# power_supply.net
KiCad netlist of a schematic drawn in Altium Designer
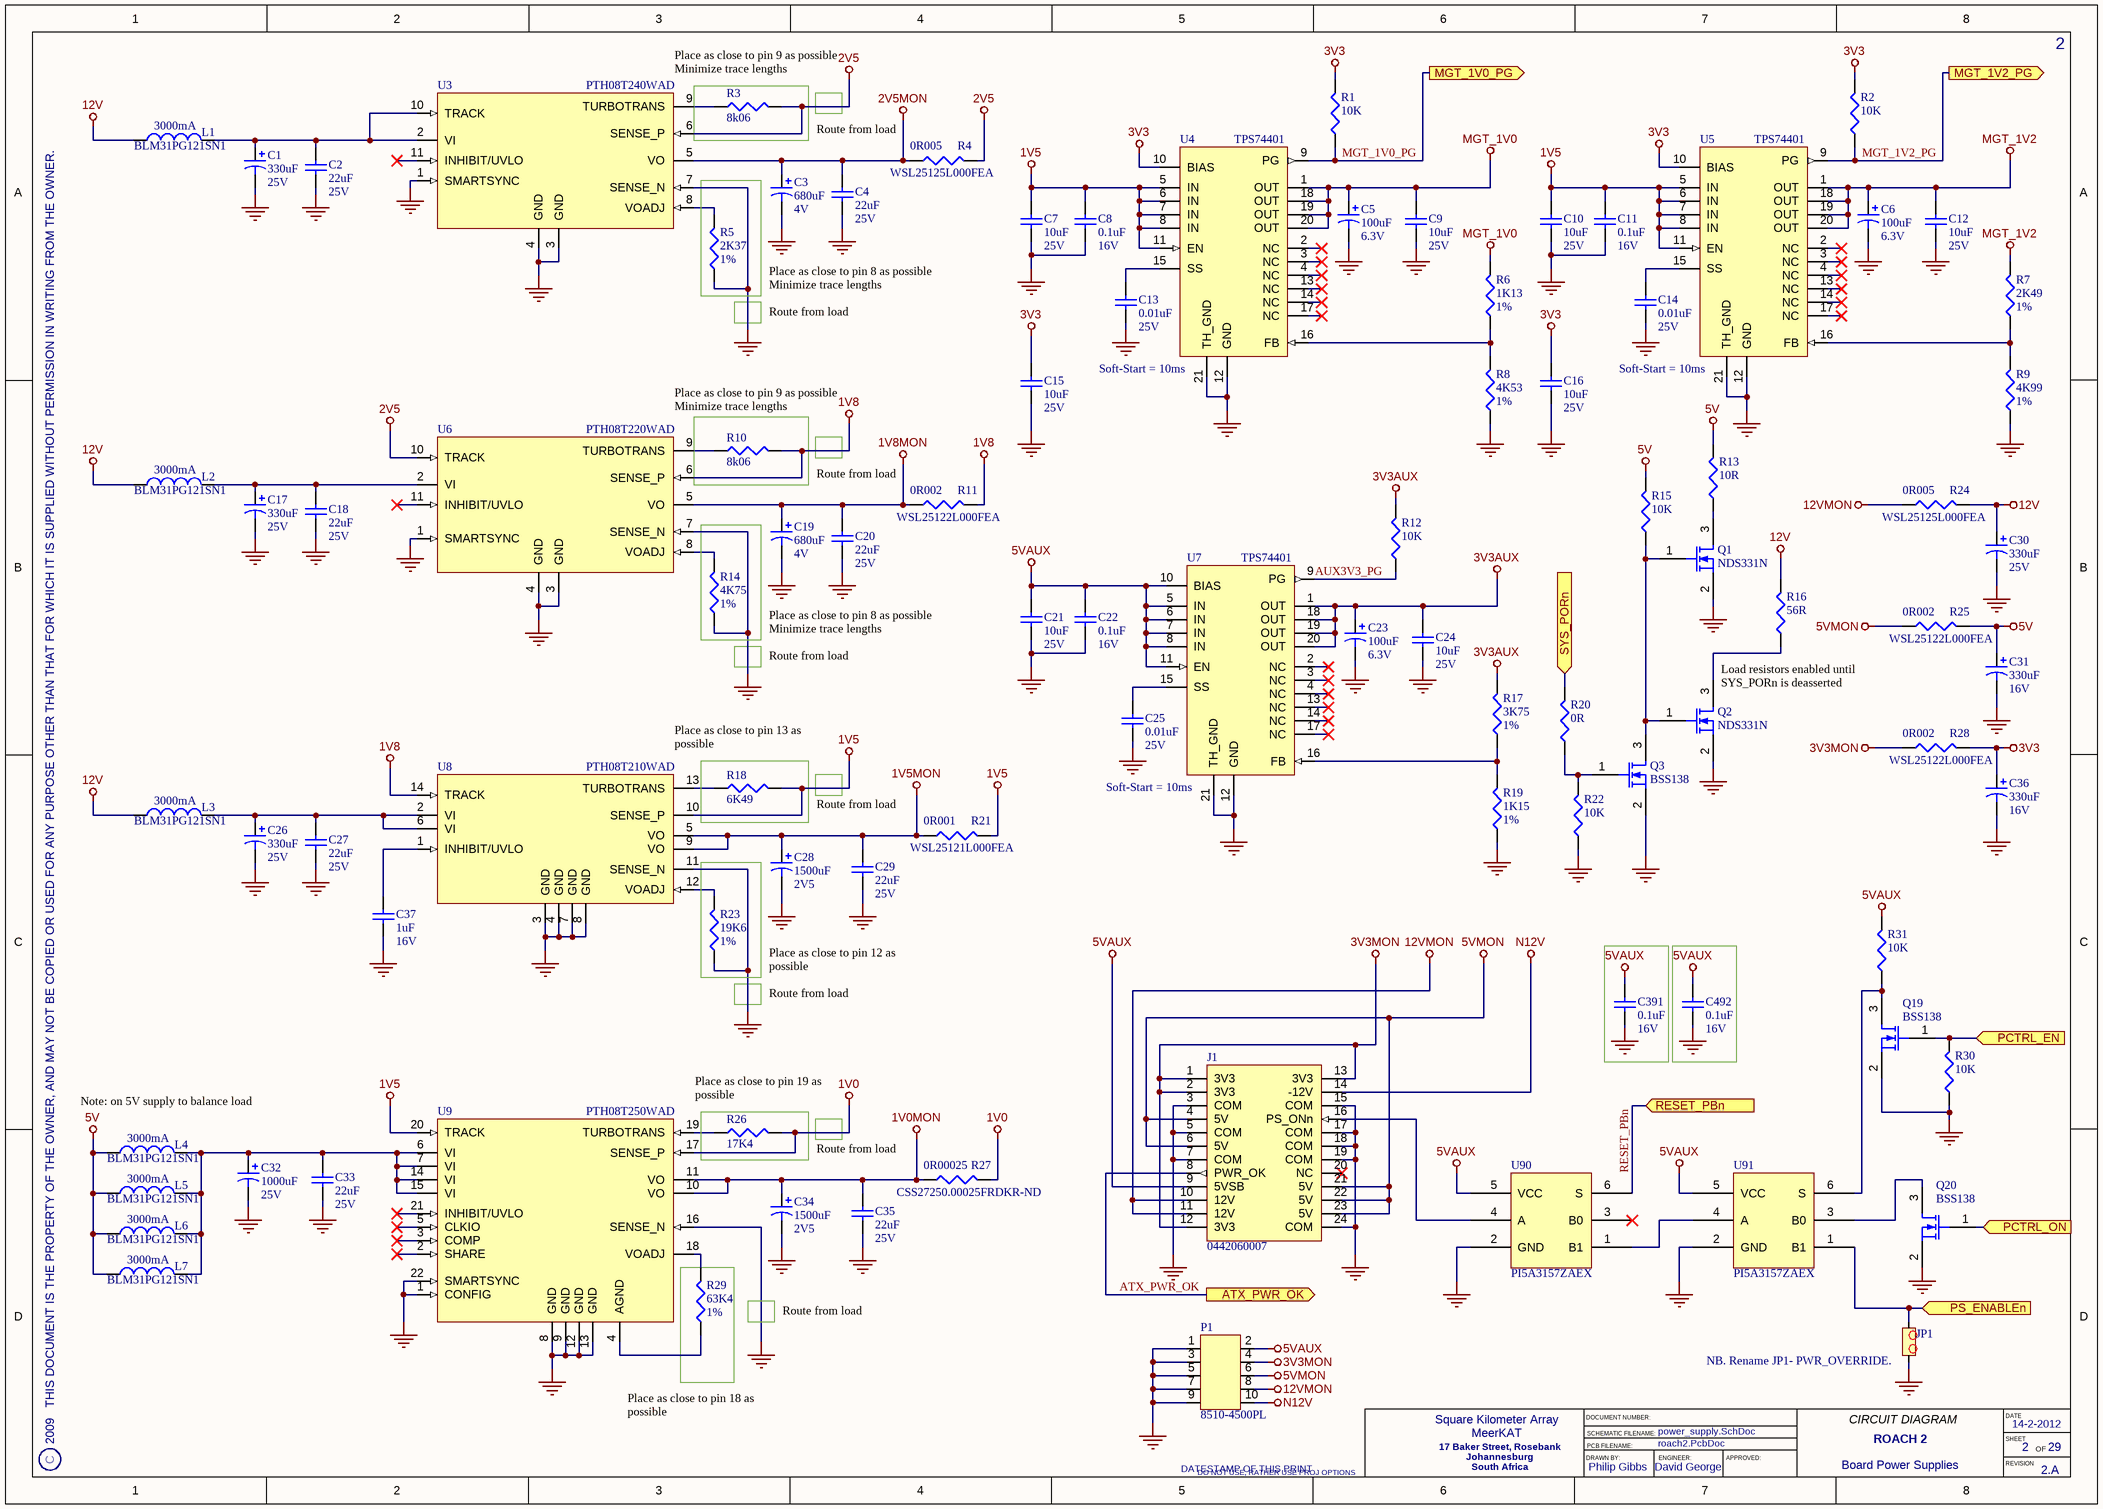
[diagram p0: power_supply.SchDoc]

(export (version "E")
  (design (tool "Eeschema 10.0.6"))
  (components
    (comp (ref "C1")
      (value "330uF")
      (footprint "EEE1CA331UP")
      (description "330uF, Surface Mount, Radial, Aluminium Electrolytic Capacitor")
      (fields
        (field (name "RATING") "25V")
        (field (name "MANUFACTURER") "PANASONIC-ECG")
        (field (name "PARTNUM") "EEE1EA331UP")
      )
      (libsource (lib "altium_db") (part "CapPol"))
    )
    (comp (ref "C2")
      (value "22uF")
      (footprint "CAPC3225X270L")
      (description "22uF, Ceramic Capacitor")
      (fields
        (field (name "RATING") "25V")
        (field (name "MANUFACTURER") "MURATA")
        (field (name "PARTNUM") "GRM32ER61E226ME15L")
      )
      (libsource (lib "altium_db") (part "CapStd"))
    )
    (comp (ref "C3")
      (value "680uF")
      (footprint "CAPMP7343X430L")
      (description "680uF, Conductive Polymer Chip Capacitor")
      (fields
        (field (name "RATING") "4V")
        (field (name "MANUFACTURER") "KEMET")
        (field (name "PARTNUM") "T520Y687M004ATE015")
      )
      (libsource (lib "altium_db") (part "CapPol"))
    )
    (comp (ref "C4")
      (value "22uF")
      (footprint "CAPC3225X270L")
      (description "22uF, Ceramic Capacitor")
      (fields
        (field (name "RATING") "25V")
        (field (name "MANUFACTURER") "MURATA")
        (field (name "PARTNUM") "GRM32ER61E226ME15L")
      )
      (libsource (lib "altium_db") (part "CapStd"))
    )
    (comp (ref "C5")
      (value "100uF")
      (footprint "CAPMP3528X210L")
      (description "100uF, Low ESR, Tantalum Capacitor")
      (fields
        (field (name "RATING") "6.3V")
        (field (name "MANUFACTURER") "AVX")
        (field (name "PARTNUM") "TPSB107M006R0200")
      )
      (libsource (lib "altium_db") (part "CapPol"))
    )
    (comp (ref "C6")
      (value "100uF")
      (footprint "CAPMP3528X210L")
      (description "100uF, Low ESR, Tantalum Capacitor")
      (fields
        (field (name "RATING") "6.3V")
        (field (name "MANUFACTURER") "AVX")
        (field (name "PARTNUM") "TPSB107M006R0200")
      )
      (libsource (lib "altium_db") (part "CapPol"))
    )
    (comp (ref "C7")
      (value "10uF")
      (footprint "CAPC3225X200L")
      (description "10uF, Ceramic Capacitor")
      (fields
        (field (name "RATING") "25V")
        (field (name "MANUFACTURER") "MURATA")
        (field (name "PARTNUM") "GRM32DR61E106KA12L")
      )
      (libsource (lib "altium_db") (part "CapStd"))
    )
    (comp (ref "C8")
      (value "0.1uF")
      (footprint "CAPC1005X60L")
      (description "0.1uF, Ceramic Capacitor")
      (fields
        (field (name "RATING") "16V")
        (field (name "MANUFACTURER") "VENKEL")
        (field (name "PARTNUM") "C0402X7R160-104KN")
      )
      (libsource (lib "altium_db") (part "CapStd"))
    )
    (comp (ref "C9")
      (value "10uF")
      (footprint "CAPC3225X200L")
      (description "10uF, Ceramic Capacitor")
      (fields
        (field (name "RATING") "25V")
        (field (name "MANUFACTURER") "MURATA")
        (field (name "PARTNUM") "GRM32DR61E106KA12L")
      )
      (libsource (lib "altium_db") (part "CapStd"))
    )
    (comp (ref "C10")
      (value "10uF")
      (footprint "CAPC3225X200L")
      (description "10uF, Ceramic Capacitor")
      (fields
        (field (name "RATING") "25V")
        (field (name "MANUFACTURER") "MURATA")
        (field (name "PARTNUM") "GRM32DR61E106KA12L")
      )
      (libsource (lib "altium_db") (part "CapStd"))
    )
    (comp (ref "C11")
      (value "0.1uF")
      (footprint "CAPC1005X60L")
      (description "0.1uF, Ceramic Capacitor")
      (fields
        (field (name "RATING") "16V")
        (field (name "MANUFACTURER") "VENKEL")
        (field (name "PARTNUM") "C0402X7R160-104KN")
      )
      (libsource (lib "altium_db") (part "CapStd"))
    )
    (comp (ref "C12")
      (value "10uF")
      (footprint "CAPC3225X200L")
      (description "10uF, Ceramic Capacitor")
      (fields
        (field (name "RATING") "25V")
        (field (name "MANUFACTURER") "MURATA")
        (field (name "PARTNUM") "GRM32DR61E106KA12L")
      )
      (libsource (lib "altium_db") (part "CapStd"))
    )
    (comp (ref "C13")
      (value "0.01uF")
      (footprint "CAPC1005X55L")
      (description "0.01uF, Ceramic Capacitor")
      (fields
        (field (name "RATING") "25V")
        (field (name "MANUFACTURER") "MURATA")
        (field (name "PARTNUM") "GRM155R71E103KA01D")
      )
      (libsource (lib "altium_db") (part "CapStd"))
    )
    (comp (ref "C14")
      (value "0.01uF")
      (footprint "CAPC1005X55L")
      (description "0.01uF, Ceramic Capacitor")
      (fields
        (field (name "RATING") "25V")
        (field (name "MANUFACTURER") "MURATA")
        (field (name "PARTNUM") "GRM155R71E103KA01D")
      )
      (libsource (lib "altium_db") (part "CapStd"))
    )
    (comp (ref "C15")
      (value "10uF")
      (footprint "CAPC3225X200L")
      (description "10uF, Ceramic Capacitor")
      (fields
        (field (name "RATING") "25V")
        (field (name "MANUFACTURER") "MURATA")
        (field (name "PARTNUM") "GRM32DR61E106KA12L")
      )
      (libsource (lib "altium_db") (part "CapStd"))
    )
    (comp (ref "C16")
      (value "10uF")
      (footprint "CAPC3225X200L")
      (description "10uF, Ceramic Capacitor")
      (fields
        (field (name "RATING") "25V")
        (field (name "MANUFACTURER") "MURATA")
        (field (name "PARTNUM") "GRM32DR61E106KA12L")
      )
      (libsource (lib "altium_db") (part "CapStd"))
    )
    (comp (ref "C17")
      (value "330uF")
      (footprint "EEE1CA331UP")
      (description "330uF, Surface Mount, Radial, Aluminium Electrolytic Capacitor")
      (fields
        (field (name "RATING") "25V")
        (field (name "MANUFACTURER") "PANASONIC-ECG")
        (field (name "PARTNUM") "EEE1EA331UP")
      )
      (libsource (lib "altium_db") (part "CapPol"))
    )
    (comp (ref "C18")
      (value "22uF")
      (footprint "CAPC3225X270L")
      (description "22uF, Ceramic Capacitor")
      (fields
        (field (name "RATING") "25V")
        (field (name "MANUFACTURER") "MURATA")
        (field (name "PARTNUM") "GRM32ER61E226ME15L")
      )
      (libsource (lib "altium_db") (part "CapStd"))
    )
    (comp (ref "C19")
      (value "680uF")
      (footprint "CAPMP7343X430L")
      (description "680uF, Conductive Polymer Chip Capacitor")
      (fields
        (field (name "RATING") "4V")
        (field (name "MANUFACTURER") "KEMET")
        (field (name "PARTNUM") "T520Y687M004ATE015")
      )
      (libsource (lib "altium_db") (part "CapPol"))
    )
    (comp (ref "C20")
      (value "22uF")
      (footprint "CAPC3225X270L")
      (description "22uF, Ceramic Capacitor")
      (fields
        (field (name "RATING") "25V")
        (field (name "MANUFACTURER") "MURATA")
        (field (name "PARTNUM") "GRM32ER61E226ME15L")
      )
      (libsource (lib "altium_db") (part "CapStd"))
    )
    (comp (ref "C21")
      (value "10uF")
      (footprint "CAPC3225X200L")
      (description "10uF, Ceramic Capacitor")
      (fields
        (field (name "RATING") "25V")
        (field (name "MANUFACTURER") "MURATA")
        (field (name "PARTNUM") "GRM32DR61E106KA12L")
      )
      (libsource (lib "altium_db") (part "CapStd"))
    )
    (comp (ref "C22")
      (value "0.1uF")
      (footprint "CAPC1005X60L")
      (description "0.1uF, Ceramic Capacitor")
      (fields
        (field (name "RATING") "16V")
        (field (name "MANUFACTURER") "VENKEL")
        (field (name "PARTNUM") "C0402X7R160-104KN")
      )
      (libsource (lib "altium_db") (part "CapStd"))
    )
    (comp (ref "C23")
      (value "100uF")
      (footprint "CAPMP3528X210L")
      (description "100uF, Low ESR, Tantalum Capacitor")
      (fields
        (field (name "RATING") "6.3V")
        (field (name "MANUFACTURER") "AVX")
        (field (name "PARTNUM") "TPSB107M006R0200")
      )
      (libsource (lib "altium_db") (part "CapPol"))
    )
    (comp (ref "C24")
      (value "10uF")
      (footprint "CAPC3225X200L")
      (description "10uF, Ceramic Capacitor")
      (fields
        (field (name "RATING") "25V")
        (field (name "MANUFACTURER") "MURATA")
        (field (name "PARTNUM") "GRM32DR61E106KA12L")
      )
      (libsource (lib "altium_db") (part "CapStd"))
    )
    (comp (ref "C25")
      (value "0.01uF")
      (footprint "CAPC1005X55L")
      (description "0.01uF, Ceramic Capacitor")
      (fields
        (field (name "RATING") "25V")
        (field (name "MANUFACTURER") "MURATA")
        (field (name "PARTNUM") "GRM155R71E103KA01D")
      )
      (libsource (lib "altium_db") (part "CapStd"))
    )
    (comp (ref "C26")
      (value "330uF")
      (footprint "EEE1CA331UP")
      (description "330uF, Surface Mount, Radial, Aluminium Electrolytic Capacitor")
      (fields
        (field (name "RATING") "25V")
        (field (name "MANUFACTURER") "PANASONIC-ECG")
        (field (name "PARTNUM") "EEE1EA331UP")
      )
      (libsource (lib "altium_db") (part "CapPol"))
    )
    (comp (ref "C27")
      (value "22uF")
      (footprint "CAPC3225X270L")
      (description "22uF, Ceramic Capacitor")
      (fields
        (field (name "RATING") "25V")
        (field (name "MANUFACTURER") "MURATA")
        (field (name "PARTNUM") "GRM32ER61E226ME15L")
      )
      (libsource (lib "altium_db") (part "CapStd"))
    )
    (comp (ref "C28")
      (value "1500uF")
      (footprint "CAPMP7343X430L")
      (description "1500uF, Conductive Polymer Chip Capacitor")
      (fields
        (field (name "RATING") "2V5")
        (field (name "MANUFACTURER") "KEMET")
        (field (name "PARTNUM") "T530X158M2R5ATE005")
      )
      (libsource (lib "altium_db") (part "CapPol"))
    )
    (comp (ref "C29")
      (value "22uF")
      (footprint "CAPC3225X270L")
      (description "22uF, Ceramic Capacitor")
      (fields
        (field (name "RATING") "25V")
        (field (name "MANUFACTURER") "MURATA")
        (field (name "PARTNUM") "GRM32ER61E226ME15L")
      )
      (libsource (lib "altium_db") (part "CapStd"))
    )
    (comp (ref "C30")
      (value "330uF")
      (footprint "EEE1CA331UP")
      (description "330uF, Surface Mount, Radial, Aluminium Electrolytic Capacitor")
      (fields
        (field (name "RATING") "25V")
        (field (name "MANUFACTURER") "PANASONIC-ECG")
        (field (name "PARTNUM") "EEE1EA331UP")
      )
      (libsource (lib "altium_db") (part "CapPol"))
    )
    (comp (ref "C31")
      (value "330uF")
      (footprint "CAPMP7263X380L")
      (description "330uF, Solid Tantalum Chip Capacitor")
      (fields
        (field (name "RATING") "16V")
        (field (name "MANUFACTURER") "VISHAY")
        (field (name "PARTNUM") "594D337X0016R2T")
      )
      (libsource (lib "altium_db") (part "CapPol"))
    )
    (comp (ref "C32")
      (value "1000uF")
      (footprint "CAPPRD750W80D1600H1500P")
      (description "1000uF, Aluminium Electrolytic Capacitor")
      (fields
        (field (name "RATING") "25V")
        (field (name "MANUFACTURER") "PANASONIC-ECG")
        (field (name "PARTNUM") "EEUFC1E102S")
      )
      (libsource (lib "altium_db") (part "CapPol"))
    )
    (comp (ref "C33")
      (value "22uF")
      (footprint "CAPC3225X270L")
      (description "22uF, Ceramic Capacitor")
      (fields
        (field (name "RATING") "25V")
        (field (name "MANUFACTURER") "MURATA")
        (field (name "PARTNUM") "GRM32ER61E226ME15L")
      )
      (libsource (lib "altium_db") (part "CapStd"))
    )
    (comp (ref "C34")
      (value "1500uF")
      (footprint "CAPMP7343X430L")
      (description "1500uF, Conductive Polymer Chip Capacitor")
      (fields
        (field (name "RATING") "2V5")
        (field (name "MANUFACTURER") "KEMET")
        (field (name "PARTNUM") "T530X158M2R5ATE005")
      )
      (libsource (lib "altium_db") (part "CapPol"))
    )
    (comp (ref "C35")
      (value "22uF")
      (footprint "CAPC3225X270L")
      (description "22uF, Ceramic Capacitor")
      (fields
        (field (name "RATING") "25V")
        (field (name "MANUFACTURER") "MURATA")
        (field (name "PARTNUM") "GRM32ER61E226ME15L")
      )
      (libsource (lib "altium_db") (part "CapStd"))
    )
    (comp (ref "C36")
      (value "330uF")
      (footprint "CAPMP7263X380L")
      (description "330uF, Solid Tantalum Chip Capacitor")
      (fields
        (field (name "RATING") "16V")
        (field (name "MANUFACTURER") "VISHAY")
        (field (name "PARTNUM") "594D337X0016R2T")
      )
      (libsource (lib "altium_db") (part "CapPol"))
    )
    (comp (ref "C37")
      (value "1uF")
      (footprint "CAPC2012X127L")
      (description "1uF, Ceramic Capacitor")
      (fields
        (field (name "MANUFACTURER") "MURATA")
        (field (name "PARTNUM") "GRM21BR61C105KA01L")
        (field (name "RATING") "16V")
      )
      (libsource (lib "altium_db") (part "CapStd"))
    )
    (comp (ref "C391")
      (value "0.1uF")
      (footprint "CAPC1005X60L")
      (description "0.1uF, Ceramic Capacitor")
      (fields
        (field (name "RATING") "16V")
        (field (name "MANUFACTURER") "VENKEL")
        (field (name "PARTNUM") "C0402X7R160-104KN")
      )
      (libsource (lib "altium_db") (part "CapStd"))
    )
    (comp (ref "C492")
      (value "0.1uF")
      (footprint "CAPC1005X60L")
      (description "0.1uF, Ceramic Capacitor")
      (fields
        (field (name "RATING") "16V")
        (field (name "MANUFACTURER") "VENKEL")
        (field (name "PARTNUM") "C0402X7R160-104KN")
      )
      (libsource (lib "altium_db") (part "CapStd"))
    )
    (comp (ref "J1")
      (value "0442060007")
      (footprint "MOLEX_0442060007")
      (description "24-Pin ATX Connector")
      (fields (field (name "PARTNUM") "0442060007") (field (name "MANUFACTURER") "Molex"))
      (libsource (lib "altium_db") (part "0442060007"))
    )
    (comp (ref "JP1")
      (value "0022032021")
      (footprint "MOLEX_0022032021")
      (description "1x2, 2.56mm, Header/Jumper")
      (fields (field (name "MANUFACTURER") "Molex"))
      (libsource (lib "altium_db") (part "con_hdr_1x2"))
    )
    (comp (ref "L1")
      (value "120R")
      (footprint "INDC3216X130L")
      (description "120 Ohm, Chip Ferrite Brad")
      (fields
        (field (name "RATING") "3000mA")
        (field (name "MANUFACTURER") "Murata")
        (field (name "PARTNUM") "BLM31PG121SN1")
        (field (name "TOLERANCE") "25%")
      )
      (libsource (lib "altium_db") (part "IndStd"))
    )
    (comp (ref "L2")
      (value "120R")
      (footprint "INDC3216X130L")
      (description "120 Ohm, Chip Ferrite Brad")
      (fields
        (field (name "RATING") "3000mA")
        (field (name "MANUFACTURER") "Murata")
        (field (name "PARTNUM") "BLM31PG121SN1")
        (field (name "TOLERANCE") "25%")
      )
      (libsource (lib "altium_db") (part "IndStd"))
    )
    (comp (ref "L3")
      (value "120R")
      (footprint "INDC3216X130L")
      (description "120 Ohm, Chip Ferrite Brad")
      (fields
        (field (name "RATING") "3000mA")
        (field (name "MANUFACTURER") "Murata")
        (field (name "PARTNUM") "BLM31PG121SN1")
        (field (name "TOLERANCE") "25%")
      )
      (libsource (lib "altium_db") (part "IndStd"))
    )
    (comp (ref "L4")
      (value "120R")
      (footprint "INDC3216X130L")
      (description "120 Ohm, Chip Ferrite Brad")
      (fields
        (field (name "RATING") "3000mA")
        (field (name "MANUFACTURER") "Murata")
        (field (name "PARTNUM") "BLM31PG121SN1")
        (field (name "TOLERANCE") "25%")
      )
      (libsource (lib "altium_db") (part "IndStd"))
    )
    (comp (ref "L5")
      (value "120R")
      (footprint "INDC3216X130L")
      (description "120 Ohm, Chip Ferrite Brad")
      (fields
        (field (name "RATING") "3000mA")
        (field (name "MANUFACTURER") "Murata")
        (field (name "PARTNUM") "BLM31PG121SN1")
        (field (name "TOLERANCE") "25%")
      )
      (libsource (lib "altium_db") (part "IndStd"))
    )
    (comp (ref "L6")
      (value "120R")
      (footprint "INDC3216X130L")
      (description "120 Ohm, Chip Ferrite Brad")
      (fields
        (field (name "RATING") "3000mA")
        (field (name "MANUFACTURER") "Murata")
        (field (name "PARTNUM") "BLM31PG121SN1")
        (field (name "TOLERANCE") "25%")
      )
      (libsource (lib "altium_db") (part "IndStd"))
    )
    (comp (ref "L7")
      (value "120R")
      (footprint "INDC3216X130L")
      (description "120 Ohm, Chip Ferrite Brad")
      (fields
        (field (name "RATING") "3000mA")
        (field (name "MANUFACTURER") "Murata")
        (field (name "PARTNUM") "BLM31PG121SN1")
        (field (name "TOLERANCE") "25%")
      )
      (libsource (lib "altium_db") (part "IndStd"))
    )
    (comp (ref "P1")
      (value "8510-4500PL")
      (footprint "3M_8510-4500PL")
      (description "2x5, 2.54 mm Pitch, Through-hole, 1 Amp, Female Header")
      (fields (field (name "PARTNUM") "8510-4500PL") (field (name "MANUFACTURER") "3M"))
      (libsource (lib "altium_db") (part "con_hdr_2x5"))
    )
    (comp (ref "Q1")
      (value "NDS331N")
      (footprint "SOT95P245X110-3N")
      (description "N-Channel Logic Level Enhancement Mode Field Effect Transistor")
      (fields (field (name "MANUFACTURER") "Fairchild Semiconductor"))
      (libsource (lib "altium_db") (part "NDS331N"))
    )
    (comp (ref "Q2")
      (value "NDS331N")
      (footprint "SOT95P245X110-3N")
      (description "N-Channel Logic Level Enhancement Mode Field Effect Transistor")
      (fields (field (name "MANUFACTURER") "Fairchild Semiconductor"))
      (libsource (lib "altium_db") (part "NDS331N"))
    )
    (comp (ref "Q3")
      (value "BSS138")
      (footprint "SOT95P245X110-3N")
      (description "N-Channel Logic Level Enhancement Mode Field Effect Transistor")
      (fields (field (name "MANUFACTURER") "Fairchild Semiconductor"))
      (libsource (lib "altium_db") (part "BSS138"))
    )
    (comp (ref "Q19")
      (value "BSS138")
      (footprint "SOT95P245X110-3N")
      (description "N-Channel Logic Level Enhancement Mode Field Effect Transistor")
      (fields (field (name "MANUFACTURER") "Fairchild Semiconductor"))
      (libsource (lib "altium_db") (part "BSS138"))
    )
    (comp (ref "Q20")
      (value "BSS138")
      (footprint "SOT95P245X110-3N")
      (description "N-Channel Logic Level Enhancement Mode Field Effect Transistor")
      (fields (field (name "MANUFACTURER") "Fairchild Semiconductor"))
      (libsource (lib "altium_db") (part "BSS138"))
    )
    (comp (ref "R1")
      (value "10K")
      (footprint "RESC1005X40L")
      (description "10K, 1.1mm x 0.5mm, Thick Film Resistor")
      (fields (field (name "MANUFACTURER") "ROYALOHM") (field (name "PARTNUM") "0402WGJ0103T1E"))
      (libsource (lib "altium_db") (part "ResStd"))
    )
    (comp (ref "R2")
      (value "10K")
      (footprint "RESC1005X40L")
      (description "10K, 1.1mm x 0.5mm, Thick Film Resistor")
      (fields (field (name "MANUFACTURER") "ROYALOHM") (field (name "PARTNUM") "0402WGJ0103T1E"))
      (libsource (lib "altium_db") (part "ResStd"))
    )
    (comp (ref "R3")
      (value "8k06")
      (footprint "RESC1005X40L")
      (description "8K06, 1.1mm x 0.5mm, Thick Film Resistor")
      (fields (field (name "Comment") "ResStd"))
      (libsource (lib "altium_db") (part "ResStd"))
    )
    (comp (ref "R4")
      (value "0R005")
      (footprint "RESC6332X90M")
      (description "5 milliohm, Power Metal Strip, Sense Resistor")
      (fields
        (field (name "MANUFACTURER") "VISHAY")
        (field (name "PARTNUM") "WSL25125L000FEA")
        (field (name "TOLERANCE") "1%")
      )
      (libsource (lib "altium_db") (part "ResStd"))
    )
    (comp (ref "R5")
      (value "2K37")
      (footprint "RESC1005X40L")
      (description "2K37, 1.1mm x 0.5mm, Thick Film Resistor")
      (fields
        (field (name "MANUFACTURER") "ROYALOHM")
        (field (name "PARTNUM") "0402WGF2371T1E")
        (field (name "TOLERANCE") "1%")
      )
      (libsource (lib "altium_db") (part "ResStd"))
    )
    (comp (ref "R6")
      (value "1K13")
      (footprint "RESC1005X40L")
      (description "1K13, 1.1mm x 0.5mm, Thick Film Resistor")
      (fields
        (field (name "MANUFACTURER") "ROYALOHM")
        (field (name "PARTNUM") "0402WGF1131T1E")
        (field (name "TOLERANCE") "1%")
      )
      (libsource (lib "altium_db") (part "ResStd"))
    )
    (comp (ref "R7")
      (value "2K49")
      (footprint "RESC1005X40L")
      (description "2K49, 1.1mm x 0.5mm, Thick Film Resistor")
      (fields
        (field (name "MANUFACTURER") "ROYALOHM")
        (field (name "PARTNUM") "0402WGF2K49T1E")
        (field (name "TOLERANCE") "1%")
      )
      (libsource (lib "altium_db") (part "ResStd"))
    )
    (comp (ref "R8")
      (value "4K53")
      (footprint "RESC1005X40L")
      (description "4K53, 1.1mm x 0.5mm, Thick Film Resistor")
      (fields
        (field (name "MANUFACTURER") "ROYALOHM")
        (field (name "PARTNUM") "0402WGF4531T1E")
        (field (name "TOLERANCE") "1%")
      )
      (libsource (lib "altium_db") (part "ResStd"))
    )
    (comp (ref "R9")
      (value "4K99")
      (footprint "RESC1005X40L")
      (description "4K99, 1.1mm x 0.5mm, Thick Film Resistor")
      (fields
        (field (name "MANUFACTURER") "ROYALOHM")
        (field (name "PARTNUM") "0402WGF4991T1E")
        (field (name "TOLERANCE") "1%")
      )
      (libsource (lib "altium_db") (part "ResStd"))
    )
    (comp (ref "R10")
      (value "8k06")
      (footprint "RESC1005X40L")
      (description "8K06, 1.1mm x 0.5mm, Thick Film Resistor")
      (fields (field (name "Comment") "ResStd"))
      (libsource (lib "altium_db") (part "ResStd"))
    )
    (comp (ref "R11")
      (value "0R002")
      (footprint "RESC6332X90M")
      (description "2 milliohm, Power Metal Strip, Sense Resistor")
      (fields
        (field (name "MANUFACTURER") "VISHAY")
        (field (name "PARTNUM") "WSL25122L000FEA")
        (field (name "TOLERANCE") "1%")
      )
      (libsource (lib "altium_db") (part "ResStd"))
    )
    (comp (ref "R12")
      (value "10K")
      (footprint "RESC1005X40L")
      (description "10K, 1.1mm x 0.5mm, Thick Film Resistor")
      (fields (field (name "MANUFACTURER") "ROYALOHM") (field (name "PARTNUM") "0402WGJ0103T1E"))
      (libsource (lib "altium_db") (part "ResStd"))
    )
    (comp (ref "R13")
      (value "10R")
      (footprint "VISHAY_AC5")
      (description "10R, Cemented Wire Round Resistor")
      (fields (field (name "MANUFACTURER") "VISHAY") (field (name "PARTNUM") "AC05000001009JLB00"))
      (libsource (lib "altium_db") (part "ResStd"))
    )
    (comp (ref "R14")
      (value "4K75")
      (footprint "RESC1005X40L")
      (description "4K75, 1.1mm x 0.5mm, Thick Film Resistor")
      (fields
        (field (name "MANUFACTURER") "ROYALOHM")
        (field (name "PARTNUM") "0402WGF4751T1E")
        (field (name "TOLERANCE") "1%")
      )
      (libsource (lib "altium_db") (part "ResStd"))
    )
    (comp (ref "R15")
      (value "10K")
      (footprint "RESC1005X40L")
      (description "10K, 1.1mm x 0.5mm, Thick Film Resistor")
      (fields (field (name "MANUFACTURER") "ROYALOHM") (field (name "PARTNUM") "0402WGJ0103T1E"))
      (libsource (lib "altium_db") (part "ResStd"))
    )
    (comp (ref "R16")
      (value "56R")
      (footprint "VISHAY_AC5")
      (description "56R, Cemented Wire Round Resistor")
      (fields (field (name "MANUFACTURER") "VISHAY") (field (name "PARTNUM") "AC05000001009JLB00"))
      (libsource (lib "altium_db") (part "ResStd"))
    )
    (comp (ref "R17")
      (value "3K75")
      (footprint "RESC1005X40L")
      (description "3K57, 1.1mm x 0.5mm, Thick Film Resistor")
      (fields
        (field (name "MANUFACTURER") "ROYALOHM")
        (field (name "PARTNUM") "0402WGF3751T1E")
        (field (name "TOLERANCE") "1%")
      )
      (libsource (lib "altium_db") (part "ResStd"))
    )
    (comp (ref "R18")
      (value "6K49")
      (footprint "RESC1005X40L")
      (description "6K49, 1.1mm x 0.5mm, Thick Film Resistor")
      (fields (field (name "Comment") "ResStd"))
      (libsource (lib "altium_db") (part "ResStd"))
    )
    (comp (ref "R19")
      (value "1K15")
      (footprint "RESC1005X40L")
      (description "1K15, 1.1mm x 0.5mm, Thick Film Resistor")
      (fields
        (field (name "MANUFACTURER") "ROYALOHM")
        (field (name "PARTNUM") "0402WGF1150T1E")
        (field (name "TOLERANCE") "1%")
      )
      (libsource (lib "altium_db") (part "ResStd"))
    )
    (comp (ref "R20")
      (value "0R")
      (footprint "RESC1005X40L")
      (description "0R, 1.1mm x 0.5mm, Thick Film Resistor")
      (fields (field (name "MANUFACTURER") "ROYALOHM") (field (name "PARTNUM") "0402WG00000T1E"))
      (libsource (lib "altium_db") (part "ResStd"))
    )
    (comp (ref "R21")
      (value "0R001")
      (footprint "RESC6332X90M")
      (description "1 milliohm, Power Metal Strip, Sense Resistor")
      (fields
        (field (name "MANUFACTURER") "VISHAY")
        (field (name "PARTNUM") "WSL25121L000FEA")
        (field (name "TOLERANCE") "1%")
      )
      (libsource (lib "altium_db") (part "ResStd"))
    )
    (comp (ref "R22")
      (value "10K")
      (footprint "RESC1005X40L")
      (description "10K, 1.1mm x 0.5mm, Thick Film Resistor")
      (fields (field (name "MANUFACTURER") "ROYALOHM") (field (name "PARTNUM") "0402WGJ0103T1E"))
      (libsource (lib "altium_db") (part "ResStd"))
    )
    (comp (ref "R23")
      (value "19K6")
      (footprint "RESC1005X40L")
      (description "19K6, 1.1mm x 0.5mm, Thick Film Resistor")
      (fields
        (field (name "MANUFACTURER") "ROYALOHM")
        (field (name "PARTNUM") "0402WGF1962T1E")
        (field (name "TOLERANCE") "1%")
      )
      (libsource (lib "altium_db") (part "ResStd"))
    )
    (comp (ref "R24")
      (value "0R005")
      (footprint "RESC6332X90M")
      (description "5 milliohm, Power Metal Strip, Sense Resistor")
      (fields
        (field (name "MANUFACTURER") "VISHAY")
        (field (name "PARTNUM") "WSL25125L000FEA")
        (field (name "TOLERANCE") "1%")
      )
      (libsource (lib "altium_db") (part "ResStd"))
    )
    (comp (ref "R25")
      (value "0R002")
      (footprint "RESC6332X90M")
      (description "2 milliohm, Power Metal Strip, Sense Resistor")
      (fields
        (field (name "MANUFACTURER") "VISHAY")
        (field (name "PARTNUM") "WSL25122L000FEA")
        (field (name "TOLERANCE") "1%")
      )
      (libsource (lib "altium_db") (part "ResStd"))
    )
    (comp (ref "R26")
      (value "17K4")
      (footprint "RESC1005X40L")
      (description "17K4, 1.1mm x 0.5mm, Thick Film Resistor")
      (fields (field (name "Comment") "ResStd"))
      (libsource (lib "altium_db") (part "ResStd"))
    )
    (comp (ref "R27")
      (value "0R00025")
      (footprint "RESC6867X140M")
      (description "0.25 milliohm, Power Metal Foil;, Sense Resistor")
      (fields
        (field (name "MANUFACTURER") "STACKPOLE")
        (field (name "PARTNUM") "CSS27250.00025FRDKR-ND")
        (field (name "TOLERANCE") "1%")
      )
      (libsource (lib "altium_db") (part "ResStd"))
    )
    (comp (ref "R28")
      (value "0R002")
      (footprint "RESC6332X90M")
      (description "2 milliohm, Power Metal Strip, Sense Resistor")
      (fields
        (field (name "MANUFACTURER") "VISHAY")
        (field (name "PARTNUM") "WSL25122L000FEA")
        (field (name "TOLERANCE") "1%")
      )
      (libsource (lib "altium_db") (part "ResStd"))
    )
    (comp (ref "R29")
      (value "63K4")
      (footprint "RESC1005X40L")
      (description "63K4, 1.1mm x 0.5mm, Thick Film Resistor")
      (fields
        (field (name "MANUFACTURER") "ROYALOHM")
        (field (name "PARTNUM") "0402WGF6342T1E")
        (field (name "TOLERANCE") "1%")
      )
      (libsource (lib "altium_db") (part "ResStd"))
    )
    (comp (ref "R30")
      (value "10K")
      (footprint "RESC1005X40L")
      (description "10K, 1.1mm x 0.5mm, Thick Film Resistor")
      (fields (field (name "MANUFACTURER") "ROYALOHM") (field (name "PARTNUM") "0402WGJ0103T1E"))
      (libsource (lib "altium_db") (part "ResStd"))
    )
    (comp (ref "R31")
      (value "10K")
      (footprint "RESC1005X40L")
      (description "10K, 1.1mm x 0.5mm, Thick Film Resistor")
      (fields (field (name "MANUFACTURER") "ROYALOHM") (field (name "PARTNUM") "0402WGJ0103T1E"))
      (libsource (lib "altium_db") (part "ResStd"))
    )
    (comp (ref "U3")
      (value "PTH08T240WAD")
      (footprint "DIP_Module_11PIN-A")
      (description "10-A, 4.5-V to 14-V INPUT, NON-ISOLATED, WIDE-OUTPUT, ADJUSTABLE POWER MODULE WITH TurboTrans")
      (fields (field (name "MANUFACTURER") "Texas Instruments"))
      (libsource (lib "altium_db") (part "PTH08T240W"))
    )
    (comp (ref "U4")
      (value "TPS74401")
      (footprint "VQFN20")
      (description "3.0A Ultra-LDO with Programmable Soft-Start")
      (fields (field (name "MANUFACTURER") "Texas Instruments"))
      (libsource (lib "altium_db") (part "TPS74401"))
    )
    (comp (ref "U5")
      (value "TPS74401")
      (footprint "VQFN20")
      (description "3.0A Ultra-LDO with Programmable Soft-Start")
      (fields (field (name "MANUFACTURER") "Texas Instruments"))
      (libsource (lib "altium_db") (part "TPS74401"))
    )
    (comp (ref "U6")
      (value "PTH08T220WAD")
      (footprint "DIP_Module_11PIN")
      (description "16-A, 4.5-V to 14-V INPUT, NON-ISOLATED, WIDE-OUTPUT, ADJUSTABLE POWER MODULE WITH TurboTrans")
      (fields (field (name "MANUFACTURER") "Texas Instruments"))
      (libsource (lib "altium_db") (part "PTH08T220W"))
    )
    (comp (ref "U7")
      (value "TPS74401")
      (footprint "VQFN20")
      (description "3.0A Ultra-LDO with Programmable Soft-Start")
      (fields (field (name "MANUFACTURER") "Texas Instruments"))
      (libsource (lib "altium_db") (part "TPS74401"))
    )
    (comp (ref "U8")
      (value "PTH08T210WAD")
      (footprint "DIP_Module_14PIN")
      (description "30-A, 5.5V-14-V INPUT, NON-ISOLATED, WIDE OUTPUT ADJUST, POWER MODULE WITH TURBOTRANS")
      (fields (field (name "MANUFACTURER") "Texas Instruments"))
      (libsource (lib "altium_db") (part "PTH08T210W"))
    )
    (comp (ref "U9")
      (value "PTH08T250WAD")
      (footprint "DIP_Module_22PIN")
      (description "50-A, 4.5-V to 14-V INPUT, NON-ISOLATED,  WIDE-OUTPUT, ADJUSTABLE POWER MODULE WITH TurboTrans")
      (fields (field (name "MANUFACTURER") "Texas Instruments"))
      (libsource (lib "altium_db") (part "PTH08T250W"))
    )
    (comp (ref "U90")
      (value "PI5A3157ZAEX")
      (footprint "SC70-6")
      (description "Low voltage SPDT Analogue Switch")
      (fields (field (name "MANUFACTURER") "PERICOM"))
      (libsource (lib "altium_db") (part "PI5A3157ZAEX"))
    )
    (comp (ref "U91")
      (value "PI5A3157ZAEX")
      (footprint "SC70-6")
      (description "Low voltage SPDT Analogue Switch")
      (fields (field (name "MANUFACTURER") "PERICOM"))
      (libsource (lib "altium_db") (part "PI5A3157ZAEX"))
    )
  )
  (nets
    (net (code "1") (name "/ATX_PWR_OK") (class "Default")
      (node (ref "J1") (pin "8") (pinfunction "PWR_OK_8") (pintype "output"))
    )
    (net (code "2") (name "/AUX3V3_PG") (class "Default")
      (node (ref "R12") (pin "1") (pinfunction "1_1") (pintype "passive"))
      (node (ref "U7") (pin "9") (pinfunction "PG_9") (pintype "output"))
    )
    (net (code "3") (name "/MGT_1V0_PG") (class "Default")
      (node (ref "R1") (pin "1") (pinfunction "1_1") (pintype "passive"))
      (node (ref "U4") (pin "9") (pinfunction "PG_9") (pintype "output"))
    )
    (net (code "4") (name "/MGT_1V2_PG") (class "Default")
      (node (ref "R2") (pin "1") (pinfunction "1_1") (pintype "passive"))
      (node (ref "U5") (pin "9") (pinfunction "PG_9") (pintype "output"))
    )
    (net (code "5") (name "/PCTRL_EN") (class "Default")
      (node (ref "Q19") (pin "1") (pinfunction "G_1") (pintype "passive"))
      (node (ref "R30") (pin "2") (pinfunction "2_2") (pintype "passive"))
    )
    (net (code "6") (name "/PCTRL_ON") (class "Default")
      (node (ref "Q20") (pin "1") (pinfunction "G_1") (pintype "passive"))
    )
    (net (code "7") (name "/PS_ENABLEn") (class "Default")
      (node (ref "JP1") (pin "1") (pinfunction "1_1") (pintype "passive"))
      (node (ref "U91") (pin "1") (pinfunction "B1_1") (pintype "passive"))
    )
    (net (code "8") (name "/RESET_PBn") (class "Default")
      (node (ref "U90") (pin "6") (pinfunction "S_6") (pintype "passive"))
    )
    (net (code "9") (name "/SYS_PORn") (class "Default")
      (node (ref "R20") (pin "2") (pinfunction "2_2") (pintype "passive"))
    )
    (net (code "10") (name "1V0") (class "Default")
      (node (ref "R26") (pin "2") (pinfunction "2_2") (pintype "passive"))
      (node (ref "R27") (pin "2") (pinfunction "2_2") (pintype "passive"))
      (node (ref "U9") (pin "17") (pinfunction "SENSE_P_17") (pintype "input"))
    )
    (net (code "11") (name "1V0MON") (class "Default")
      (node (ref "C34") (pin "1") (pinfunction "1_1") (pintype "passive"))
      (node (ref "C35") (pin "2") (pinfunction "2_2") (pintype "passive"))
      (node (ref "R27") (pin "1") (pinfunction "1_1") (pintype "passive"))
      (node (ref "U9") (pin "10") (pinfunction "VO_10") (pintype "power_in"))
      (node (ref "U9") (pin "11") (pinfunction "VO_11") (pintype "power_in"))
    )
    (net (code "12") (name "1V5") (class "Default")
      (node (ref "C10") (pin "2") (pinfunction "2_2") (pintype "passive"))
      (node (ref "C11") (pin "2") (pinfunction "2_2") (pintype "passive"))
      (node (ref "C7") (pin "2") (pinfunction "2_2") (pintype "passive"))
      (node (ref "C8") (pin "2") (pinfunction "2_2") (pintype "passive"))
      (node (ref "R18") (pin "2") (pinfunction "2_2") (pintype "passive"))
      (node (ref "R21") (pin "2") (pinfunction "2_2") (pintype "passive"))
      (node (ref "U4") (pin "11") (pinfunction "EN_11") (pintype "input"))
      (node (ref "U4") (pin "5") (pinfunction "IN_5") (pintype "power_in"))
      (node (ref "U4") (pin "6") (pinfunction "IN_6") (pintype "power_in"))
      (node (ref "U4") (pin "7") (pinfunction "IN_7") (pintype "power_in"))
      (node (ref "U4") (pin "8") (pinfunction "IN_8") (pintype "power_in"))
      (node (ref "U5") (pin "11") (pinfunction "EN_11") (pintype "input"))
      (node (ref "U5") (pin "5") (pinfunction "IN_5") (pintype "power_in"))
      (node (ref "U5") (pin "6") (pinfunction "IN_6") (pintype "power_in"))
      (node (ref "U5") (pin "7") (pinfunction "IN_7") (pintype "power_in"))
      (node (ref "U5") (pin "8") (pinfunction "IN_8") (pintype "power_in"))
      (node (ref "U8") (pin "10") (pinfunction "SENSE_P_10") (pintype "power_in"))
      (node (ref "U9") (pin "20") (pinfunction "TRACK_20") (pintype "input"))
    )
    (net (code "13") (name "1V5MON") (class "Default")
      (node (ref "C28") (pin "1") (pinfunction "1_1") (pintype "passive"))
      (node (ref "C29") (pin "2") (pinfunction "2_2") (pintype "passive"))
      (node (ref "R21") (pin "1") (pinfunction "1_1") (pintype "passive"))
      (node (ref "U8") (pin "5") (pinfunction "VO_5") (pintype "power_in"))
      (node (ref "U8") (pin "9") (pinfunction "VO_9") (pintype "power_in"))
    )
    (net (code "14") (name "1V8") (class "Default")
      (node (ref "R10") (pin "2") (pinfunction "2_2") (pintype "passive"))
      (node (ref "R11") (pin "2") (pinfunction "2_2") (pintype "passive"))
      (node (ref "U6") (pin "6") (pinfunction "SENSE_P_6") (pintype "input"))
      (node (ref "U8") (pin "14") (pinfunction "TRACK_14") (pintype "input"))
    )
    (net (code "15") (name "1V8MON") (class "Default")
      (node (ref "C19") (pin "1") (pinfunction "1_1") (pintype "passive"))
      (node (ref "C20") (pin "2") (pinfunction "2_2") (pintype "passive"))
      (node (ref "R11") (pin "1") (pinfunction "1_1") (pintype "passive"))
      (node (ref "U6") (pin "5") (pinfunction "VO_5") (pintype "power_in"))
    )
    (net (code "16") (name "2V5") (class "Default")
      (node (ref "R3") (pin "2") (pinfunction "2_2") (pintype "passive"))
      (node (ref "R4") (pin "2") (pinfunction "2_2") (pintype "passive"))
      (node (ref "U3") (pin "6") (pinfunction "SENSE_P_6") (pintype "input"))
      (node (ref "U6") (pin "10") (pinfunction "TRACK_10") (pintype "input"))
    )
    (net (code "17") (name "2V5MON") (class "Default")
      (node (ref "C3") (pin "1") (pinfunction "1_1") (pintype "passive"))
      (node (ref "C4") (pin "2") (pinfunction "2_2") (pintype "passive"))
      (node (ref "R4") (pin "1") (pinfunction "1_1") (pintype "passive"))
      (node (ref "U3") (pin "5") (pinfunction "VO_5") (pintype "power_in"))
    )
    (net (code "18") (name "3V3") (class "Default")
      (node (ref "C15") (pin "2") (pinfunction "2_2") (pintype "passive"))
      (node (ref "C16") (pin "2") (pinfunction "2_2") (pintype "passive"))
      (node (ref "C36") (pin "1") (pinfunction "1_1") (pintype "passive"))
      (node (ref "R1") (pin "2") (pinfunction "2_2") (pintype "passive"))
      (node (ref "R2") (pin "2") (pinfunction "2_2") (pintype "passive"))
      (node (ref "R28") (pin "2") (pinfunction "2_2") (pintype "passive"))
      (node (ref "U4") (pin "10") (pinfunction "BIAS_10") (pintype "power_in"))
      (node (ref "U5") (pin "10") (pinfunction "BIAS_10") (pintype "power_in"))
    )
    (net (code "19") (name "3V3AUX") (class "Default")
      (node (ref "C23") (pin "1") (pinfunction "1_1") (pintype "passive"))
      (node (ref "C24") (pin "2") (pinfunction "2_2") (pintype "passive"))
      (node (ref "R12") (pin "2") (pinfunction "2_2") (pintype "passive"))
      (node (ref "R17") (pin "2") (pinfunction "2_2") (pintype "passive"))
      (node (ref "U7") (pin "1") (pinfunction "OUT_1") (pintype "power_in"))
      (node (ref "U7") (pin "18") (pinfunction "OUT_18") (pintype "power_in"))
      (node (ref "U7") (pin "19") (pinfunction "OUT_19") (pintype "power_in"))
      (node (ref "U7") (pin "20") (pinfunction "OUT_20") (pintype "power_in"))
    )
    (net (code "20") (name "3V3MON") (class "Default")
      (node (ref "J1") (pin "1") (pinfunction "3V3_1") (pintype "power_in"))
      (node (ref "J1") (pin "12") (pinfunction "3V3_12") (pintype "power_in"))
      (node (ref "J1") (pin "13") (pinfunction "3V3_13") (pintype "power_in"))
      (node (ref "J1") (pin "2") (pinfunction "3V3_2") (pintype "power_in"))
      (node (ref "P1") (pin "4") (pinfunction "4_4") (pintype "passive"))
      (node (ref "R28") (pin "1") (pinfunction "1_1") (pintype "passive"))
    )
    (net (code "21") (name "5V") (class "Default")
      (node (ref "C31") (pin "1") (pinfunction "1_1") (pintype "passive"))
      (node (ref "L4") (pin "1") (pinfunction "1_1") (pintype "passive"))
      (node (ref "L5") (pin "1") (pinfunction "1_1") (pintype "passive"))
      (node (ref "L6") (pin "1") (pinfunction "1_1") (pintype "passive"))
      (node (ref "L7") (pin "1") (pinfunction "1_1") (pintype "passive"))
      (node (ref "R13") (pin "2") (pinfunction "2_2") (pintype "passive"))
      (node (ref "R15") (pin "2") (pinfunction "2_2") (pintype "passive"))
      (node (ref "R25") (pin "2") (pinfunction "2_2") (pintype "passive"))
    )
    (net (code "22") (name "5VAUX") (class "Default")
      (node (ref "C21") (pin "2") (pinfunction "2_2") (pintype "passive"))
      (node (ref "C22") (pin "2") (pinfunction "2_2") (pintype "passive"))
      (node (ref "C391") (pin "2") (pinfunction "2_2") (pintype "passive"))
      (node (ref "C492") (pin "2") (pinfunction "2_2") (pintype "passive"))
      (node (ref "J1") (pin "9") (pinfunction "5VSB_9") (pintype "power_in"))
      (node (ref "P1") (pin "2") (pinfunction "2_2") (pintype "passive"))
      (node (ref "R31") (pin "2") (pinfunction "2_2") (pintype "passive"))
      (node (ref "U7") (pin "10") (pinfunction "BIAS_10") (pintype "power_in"))
      (node (ref "U7") (pin "11") (pinfunction "EN_11") (pintype "input"))
      (node (ref "U7") (pin "5") (pinfunction "IN_5") (pintype "power_in"))
      (node (ref "U7") (pin "6") (pinfunction "IN_6") (pintype "power_in"))
      (node (ref "U7") (pin "7") (pinfunction "IN_7") (pintype "power_in"))
      (node (ref "U7") (pin "8") (pinfunction "IN_8") (pintype "power_in"))
      (node (ref "U90") (pin "5") (pinfunction "VCC_5") (pintype "passive"))
      (node (ref "U91") (pin "5") (pinfunction "VCC_5") (pintype "passive"))
    )
    (net (code "23") (name "5VMON") (class "Default")
      (node (ref "J1") (pin "21") (pinfunction "5V_21") (pintype "power_in"))
      (node (ref "J1") (pin "22") (pinfunction "5V_22") (pintype "power_in"))
      (node (ref "J1") (pin "23") (pinfunction "5V_23") (pintype "power_in"))
      (node (ref "J1") (pin "4") (pinfunction "5V_4") (pintype "power_in"))
      (node (ref "J1") (pin "6") (pinfunction "5V_6") (pintype "power_in"))
      (node (ref "P1") (pin "6") (pinfunction "6_6") (pintype "passive"))
      (node (ref "R25") (pin "1") (pinfunction "1_1") (pintype "passive"))
    )
    (net (code "24") (name "12V") (class "Default")
      (node (ref "C30") (pin "1") (pinfunction "1_1") (pintype "passive"))
      (node (ref "L1") (pin "1") (pinfunction "1_1") (pintype "passive"))
      (node (ref "L2") (pin "1") (pinfunction "1_1") (pintype "passive"))
      (node (ref "L3") (pin "1") (pinfunction "1_1") (pintype "passive"))
      (node (ref "R16") (pin "2") (pinfunction "2_2") (pintype "passive"))
      (node (ref "R24") (pin "2") (pinfunction "2_2") (pintype "passive"))
    )
    (net (code "25") (name "12VMON") (class "Default")
      (node (ref "J1") (pin "10") (pinfunction "12V_10") (pintype "power_in"))
      (node (ref "J1") (pin "11") (pinfunction "12V_11") (pintype "power_in"))
      (node (ref "P1") (pin "8") (pinfunction "8_8") (pintype "passive"))
      (node (ref "R24") (pin "1") (pinfunction "1_1") (pintype "passive"))
    )
    (net (code "26") (name "GND") (class "Default")
      (node (ref "C1") (pin "2") (pinfunction "2_2") (pintype "passive"))
      (node (ref "C10") (pin "1") (pinfunction "1_1") (pintype "passive"))
      (node (ref "C11") (pin "1") (pinfunction "1_1") (pintype "passive"))
      (node (ref "C12") (pin "1") (pinfunction "1_1") (pintype "passive"))
      (node (ref "C13") (pin "1") (pinfunction "1_1") (pintype "passive"))
      (node (ref "C14") (pin "1") (pinfunction "1_1") (pintype "passive"))
      (node (ref "C15") (pin "1") (pinfunction "1_1") (pintype "passive"))
      (node (ref "C16") (pin "1") (pinfunction "1_1") (pintype "passive"))
      (node (ref "C17") (pin "2") (pinfunction "2_2") (pintype "passive"))
      (node (ref "C18") (pin "1") (pinfunction "1_1") (pintype "passive"))
      (node (ref "C19") (pin "2") (pinfunction "2_2") (pintype "passive"))
      (node (ref "C2") (pin "1") (pinfunction "1_1") (pintype "passive"))
      (node (ref "C20") (pin "1") (pinfunction "1_1") (pintype "passive"))
      (node (ref "C21") (pin "1") (pinfunction "1_1") (pintype "passive"))
      (node (ref "C22") (pin "1") (pinfunction "1_1") (pintype "passive"))
      (node (ref "C23") (pin "2") (pinfunction "2_2") (pintype "passive"))
      (node (ref "C24") (pin "1") (pinfunction "1_1") (pintype "passive"))
      (node (ref "C25") (pin "1") (pinfunction "1_1") (pintype "passive"))
      (node (ref "C26") (pin "2") (pinfunction "2_2") (pintype "passive"))
      (node (ref "C27") (pin "1") (pinfunction "1_1") (pintype "passive"))
      (node (ref "C28") (pin "2") (pinfunction "2_2") (pintype "passive"))
      (node (ref "C29") (pin "1") (pinfunction "1_1") (pintype "passive"))
      (node (ref "C3") (pin "2") (pinfunction "2_2") (pintype "passive"))
      (node (ref "C30") (pin "2") (pinfunction "2_2") (pintype "passive"))
      (node (ref "C31") (pin "2") (pinfunction "2_2") (pintype "passive"))
      (node (ref "C32") (pin "2") (pinfunction "2_2") (pintype "passive"))
      (node (ref "C33") (pin "1") (pinfunction "1_1") (pintype "passive"))
      (node (ref "C34") (pin "2") (pinfunction "2_2") (pintype "passive"))
      (node (ref "C35") (pin "1") (pinfunction "1_1") (pintype "passive"))
      (node (ref "C36") (pin "2") (pinfunction "2_2") (pintype "passive"))
      (node (ref "C37") (pin "2") (pinfunction "2_2") (pintype "passive"))
      (node (ref "C391") (pin "1") (pinfunction "1_1") (pintype "passive"))
      (node (ref "C4") (pin "1") (pinfunction "1_1") (pintype "passive"))
      (node (ref "C492") (pin "1") (pinfunction "1_1") (pintype "passive"))
      (node (ref "C5") (pin "2") (pinfunction "2_2") (pintype "passive"))
      (node (ref "C6") (pin "2") (pinfunction "2_2") (pintype "passive"))
      (node (ref "C7") (pin "1") (pinfunction "1_1") (pintype "passive"))
      (node (ref "C8") (pin "1") (pinfunction "1_1") (pintype "passive"))
      (node (ref "C9") (pin "1") (pinfunction "1_1") (pintype "passive"))
      (node (ref "J1") (pin "15") (pinfunction "COM_15") (pintype "power_in"))
      (node (ref "J1") (pin "17") (pinfunction "COM_17") (pintype "power_in"))
      (node (ref "J1") (pin "18") (pinfunction "COM_18") (pintype "power_in"))
      (node (ref "J1") (pin "19") (pinfunction "COM_19") (pintype "power_in"))
      (node (ref "J1") (pin "24") (pinfunction "COM_24") (pintype "power_in"))
      (node (ref "J1") (pin "3") (pinfunction "COM_3") (pintype "power_in"))
      (node (ref "J1") (pin "5") (pinfunction "COM_5") (pintype "power_in"))
      (node (ref "J1") (pin "7") (pinfunction "COM_7") (pintype "power_in"))
      (node (ref "JP1") (pin "2") (pinfunction "2_2") (pintype "passive"))
      (node (ref "P1") (pin "1") (pinfunction "1_1") (pintype "passive"))
      (node (ref "P1") (pin "3") (pinfunction "3_3") (pintype "passive"))
      (node (ref "P1") (pin "5") (pinfunction "5_5") (pintype "passive"))
      (node (ref "P1") (pin "7") (pinfunction "7_7") (pintype "passive"))
      (node (ref "P1") (pin "9") (pinfunction "9_9") (pintype "passive"))
      (node (ref "Q1") (pin "2") (pinfunction "S_2") (pintype "passive"))
      (node (ref "Q19") (pin "2") (pinfunction "S_2") (pintype "passive"))
      (node (ref "Q2") (pin "2") (pinfunction "S_2") (pintype "passive"))
      (node (ref "Q20") (pin "2") (pinfunction "S_2") (pintype "passive"))
      (node (ref "Q3") (pin "2") (pinfunction "S_2") (pintype "passive"))
      (node (ref "R14") (pin "1") (pinfunction "1_1") (pintype "passive"))
      (node (ref "R19") (pin "1") (pinfunction "1_1") (pintype "passive"))
      (node (ref "R22") (pin "1") (pinfunction "1_1") (pintype "passive"))
      (node (ref "R23") (pin "1") (pinfunction "1_1") (pintype "passive"))
      (node (ref "R30") (pin "1") (pinfunction "1_1") (pintype "passive"))
      (node (ref "R5") (pin "1") (pinfunction "1_1") (pintype "passive"))
      (node (ref "R8") (pin "1") (pinfunction "1_1") (pintype "passive"))
      (node (ref "R9") (pin "1") (pinfunction "1_1") (pintype "passive"))
      (node (ref "U3") (pin "1") (pinfunction "SMARTSYNC_1") (pintype "input"))
      (node (ref "U3") (pin "3") (pinfunction "GND_3") (pintype "power_in"))
      (node (ref "U3") (pin "4") (pinfunction "GND_4") (pintype "power_in"))
      (node (ref "U3") (pin "7") (pinfunction "SENSE_N_7") (pintype "input"))
      (node (ref "U4") (pin "12") (pinfunction "GND_12") (pintype "power_in"))
      (node (ref "U4") (pin "21") (pinfunction "TH_GND_21") (pintype "power_in"))
      (node (ref "U5") (pin "12") (pinfunction "GND_12") (pintype "power_in"))
      (node (ref "U5") (pin "21") (pinfunction "TH_GND_21") (pintype "power_in"))
      (node (ref "U6") (pin "1") (pinfunction "SMARTSYNC_1") (pintype "input"))
      (node (ref "U6") (pin "3") (pinfunction "GND_3") (pintype "power_in"))
      (node (ref "U6") (pin "4") (pinfunction "GND_4") (pintype "power_in"))
      (node (ref "U6") (pin "7") (pinfunction "SENSE_N_7") (pintype "input"))
      (node (ref "U7") (pin "12") (pinfunction "GND_12") (pintype "power_in"))
      (node (ref "U7") (pin "21") (pinfunction "TH_GND_21") (pintype "power_in"))
      (node (ref "U8") (pin "11") (pinfunction "SENSE_N_11") (pintype "power_in"))
      (node (ref "U8") (pin "3") (pinfunction "GND_3") (pintype "power_in"))
      (node (ref "U8") (pin "4") (pinfunction "GND_4") (pintype "power_in"))
      (node (ref "U8") (pin "7") (pinfunction "GND_7") (pintype "power_in"))
      (node (ref "U8") (pin "8") (pinfunction "GND_8") (pintype "power_in"))
      (node (ref "U9") (pin "1") (pinfunction "CONFIG_1") (pintype "input"))
      (node (ref "U9") (pin "12") (pinfunction "GND_12") (pintype "power_in"))
      (node (ref "U9") (pin "13") (pinfunction "GND_13") (pintype "power_in"))
      (node (ref "U9") (pin "16") (pinfunction "SENSE_N_16") (pintype "input"))
      (node (ref "U9") (pin "22") (pinfunction "SMARTSYNC_22") (pintype "input"))
      (node (ref "U9") (pin "8") (pinfunction "GND_8") (pintype "power_in"))
      (node (ref "U9") (pin "9") (pinfunction "GND_9") (pintype "power_in"))
      (node (ref "U90") (pin "2") (pinfunction "GND_2") (pintype "passive"))
      (node (ref "U91") (pin "2") (pinfunction "GND_2") (pintype "passive"))
    )
    (net (code "27") (name "MGT_1V0") (class "Default")
      (node (ref "C5") (pin "1") (pinfunction "1_1") (pintype "passive"))
      (node (ref "C9") (pin "2") (pinfunction "2_2") (pintype "passive"))
      (node (ref "R6") (pin "2") (pinfunction "2_2") (pintype "passive"))
      (node (ref "U4") (pin "1") (pinfunction "OUT_1") (pintype "power_in"))
      (node (ref "U4") (pin "18") (pinfunction "OUT_18") (pintype "power_in"))
      (node (ref "U4") (pin "19") (pinfunction "OUT_19") (pintype "power_in"))
      (node (ref "U4") (pin "20") (pinfunction "OUT_20") (pintype "power_in"))
    )
    (net (code "28") (name "MGT_1V2") (class "Default")
      (node (ref "C12") (pin "2") (pinfunction "2_2") (pintype "passive"))
      (node (ref "C6") (pin "1") (pinfunction "1_1") (pintype "passive"))
      (node (ref "R7") (pin "2") (pinfunction "2_2") (pintype "passive"))
      (node (ref "U5") (pin "1") (pinfunction "OUT_1") (pintype "power_in"))
      (node (ref "U5") (pin "18") (pinfunction "OUT_18") (pintype "power_in"))
      (node (ref "U5") (pin "19") (pinfunction "OUT_19") (pintype "power_in"))
      (node (ref "U5") (pin "20") (pinfunction "OUT_20") (pintype "power_in"))
    )
    (net (code "29") (name "N12V") (class "Default")
      (node (ref "J1") (pin "14") (pinfunction "-12V_14") (pintype "power_in"))
      (node (ref "P1") (pin "10") (pinfunction "10_10") (pintype "passive"))
    )
    (net (code "30") (name "Net-(C26-Pad1)") (class "Default")
      (node (ref "C26") (pin "1") (pinfunction "1_1") (pintype "passive"))
      (node (ref "C27") (pin "2") (pinfunction "2_2") (pintype "passive"))
      (node (ref "L3") (pin "2") (pinfunction "2_2") (pintype "passive"))
      (node (ref "U8") (pin "2") (pinfunction "VI_2") (pintype "power_in"))
      (node (ref "U8") (pin "6") (pinfunction "VI_6") (pintype "power_in"))
    )
    (net (code "31") (name "Net-(C32-Pad1)") (class "Default")
      (node (ref "C32") (pin "1") (pinfunction "1_1") (pintype "passive"))
      (node (ref "C33") (pin "2") (pinfunction "2_2") (pintype "passive"))
      (node (ref "L4") (pin "2") (pinfunction "2_2") (pintype "passive"))
      (node (ref "L5") (pin "2") (pinfunction "2_2") (pintype "passive"))
      (node (ref "L6") (pin "2") (pinfunction "2_2") (pintype "passive"))
      (node (ref "L7") (pin "2") (pinfunction "2_2") (pintype "passive"))
      (node (ref "U9") (pin "14") (pinfunction "VI_14") (pintype "power_in"))
      (node (ref "U9") (pin "15") (pinfunction "VI_15") (pintype "power_in"))
      (node (ref "U9") (pin "6") (pinfunction "VI_6") (pintype "power_in"))
      (node (ref "U9") (pin "7") (pinfunction "VI_7") (pintype "power_in"))
    )
    (net (code "32") (name "Net-(J1-PS_ONn)") (class "Default")
      (node (ref "J1") (pin "16") (pinfunction "PS_ONn_16") (pintype "input"))
      (node (ref "U90") (pin "4") (pinfunction "A_4") (pintype "passive"))
    )
    (net (code "33") (name "Net-(Q1-D)") (class "Default")
      (node (ref "Q1") (pin "3") (pinfunction "D_3") (pintype "passive"))
      (node (ref "R13") (pin "1") (pinfunction "1_1") (pintype "passive"))
    )
    (net (code "34") (name "Net-(Q1-G)") (class "Default")
      (node (ref "Q1") (pin "1") (pinfunction "G_1") (pintype "passive"))
      (node (ref "Q2") (pin "1") (pinfunction "G_1") (pintype "passive"))
      (node (ref "Q3") (pin "3") (pinfunction "D_3") (pintype "passive"))
      (node (ref "R15") (pin "1") (pinfunction "1_1") (pintype "passive"))
    )
    (net (code "35") (name "Net-(Q2-D)") (class "Default")
      (node (ref "Q2") (pin "3") (pinfunction "D_3") (pintype "passive"))
      (node (ref "R16") (pin "1") (pinfunction "1_1") (pintype "passive"))
    )
    (net (code "36") (name "Net-(Q3-G)") (class "Default")
      (node (ref "Q3") (pin "1") (pinfunction "G_1") (pintype "passive"))
      (node (ref "R20") (pin "1") (pinfunction "1_1") (pintype "passive"))
      (node (ref "R22") (pin "2") (pinfunction "2_2") (pintype "passive"))
    )
    (net (code "37") (name "Net-(Q19-D)") (class "Default")
      (node (ref "Q19") (pin "3") (pinfunction "D_3") (pintype "passive"))
      (node (ref "R31") (pin "1") (pinfunction "1_1") (pintype "passive"))
      (node (ref "U91") (pin "6") (pinfunction "S_6") (pintype "passive"))
    )
    (net (code "38") (name "Net-(Q20-D)") (class "Default")
      (node (ref "Q20") (pin "3") (pinfunction "D_3") (pintype "passive"))
      (node (ref "U91") (pin "3") (pinfunction "B0_3") (pintype "passive"))
    )
    (net (code "39") (name "Net-(U3-TRACK)") (class "Default")
      (node (ref "C1") (pin "1") (pinfunction "1_1") (pintype "passive"))
      (node (ref "C2") (pin "2") (pinfunction "2_2") (pintype "passive"))
      (node (ref "L1") (pin "2") (pinfunction "2_2") (pintype "passive"))
      (node (ref "U3") (pin "10") (pinfunction "TRACK_10") (pintype "input"))
      (node (ref "U3") (pin "2") (pinfunction "VI_2") (pintype "power_in"))
    )
    (net (code "40") (name "Net-(U3-TURBOTRANS)") (class "Default")
      (node (ref "R3") (pin "1") (pinfunction "1_1") (pintype "passive"))
      (node (ref "U3") (pin "9") (pinfunction "TURBOTRANS_9") (pintype "power_in"))
    )
    (net (code "41") (name "Net-(U3-VOADJ)") (class "Default")
      (node (ref "R5") (pin "2") (pinfunction "2_2") (pintype "passive"))
      (node (ref "U3") (pin "8") (pinfunction "VOADJ_8") (pintype "input"))
    )
    (net (code "42") (name "Net-(U4-FB)") (class "Default")
      (node (ref "R6") (pin "1") (pinfunction "1_1") (pintype "passive"))
      (node (ref "R8") (pin "2") (pinfunction "2_2") (pintype "passive"))
      (node (ref "U4") (pin "16") (pinfunction "FB_16") (pintype "input"))
    )
    (net (code "43") (name "Net-(U4-SS)") (class "Default")
      (node (ref "C13") (pin "2") (pinfunction "2_2") (pintype "passive"))
      (node (ref "U4") (pin "15") (pinfunction "SS_15") (pintype "passive"))
    )
    (net (code "44") (name "Net-(U5-FB)") (class "Default")
      (node (ref "R7") (pin "1") (pinfunction "1_1") (pintype "passive"))
      (node (ref "R9") (pin "2") (pinfunction "2_2") (pintype "passive"))
      (node (ref "U5") (pin "16") (pinfunction "FB_16") (pintype "input"))
    )
    (net (code "45") (name "Net-(U5-SS)") (class "Default")
      (node (ref "C14") (pin "2") (pinfunction "2_2") (pintype "passive"))
      (node (ref "U5") (pin "15") (pinfunction "SS_15") (pintype "passive"))
    )
    (net (code "46") (name "Net-(U6-TURBOTRANS)") (class "Default")
      (node (ref "R10") (pin "1") (pinfunction "1_1") (pintype "passive"))
      (node (ref "U6") (pin "9") (pinfunction "TURBOTRANS_9") (pintype "power_in"))
    )
    (net (code "47") (name "Net-(U6-VI)") (class "Default")
      (node (ref "C17") (pin "1") (pinfunction "1_1") (pintype "passive"))
      (node (ref "C18") (pin "2") (pinfunction "2_2") (pintype "passive"))
      (node (ref "L2") (pin "2") (pinfunction "2_2") (pintype "passive"))
      (node (ref "U6") (pin "2") (pinfunction "VI_2") (pintype "power_in"))
    )
    (net (code "48") (name "Net-(U6-VOADJ)") (class "Default")
      (node (ref "R14") (pin "2") (pinfunction "2_2") (pintype "passive"))
      (node (ref "U6") (pin "8") (pinfunction "VOADJ_8") (pintype "input"))
    )
    (net (code "49") (name "Net-(U7-FB)") (class "Default")
      (node (ref "R17") (pin "1") (pinfunction "1_1") (pintype "passive"))
      (node (ref "R19") (pin "2") (pinfunction "2_2") (pintype "passive"))
      (node (ref "U7") (pin "16") (pinfunction "FB_16") (pintype "input"))
    )
    (net (code "50") (name "Net-(U7-SS)") (class "Default")
      (node (ref "C25") (pin "2") (pinfunction "2_2") (pintype "passive"))
      (node (ref "U7") (pin "15") (pinfunction "SS_15") (pintype "passive"))
    )
    (net (code "51") (name "Net-(U8-INHIBIT{slash}UVLO)") (class "Default")
      (node (ref "C37") (pin "1") (pinfunction "1_1") (pintype "passive"))
      (node (ref "U8") (pin "1") (pinfunction "INHIBIT/UVLO_1") (pintype "input"))
    )
    (net (code "52") (name "Net-(U8-TURBOTRANS)") (class "Default")
      (node (ref "R18") (pin "1") (pinfunction "1_1") (pintype "passive"))
      (node (ref "U8") (pin "13") (pinfunction "TURBOTRANS_13") (pintype "power_in"))
    )
    (net (code "53") (name "Net-(U8-VOADJ)") (class "Default")
      (node (ref "R23") (pin "2") (pinfunction "2_2") (pintype "passive"))
      (node (ref "U8") (pin "12") (pinfunction "VOADJ_12") (pintype "input"))
    )
    (net (code "54") (name "Net-(U9-AGND)") (class "Default")
      (node (ref "R29") (pin "1") (pinfunction "1_1") (pintype "passive"))
      (node (ref "U9") (pin "4") (pinfunction "AGND_4") (pintype "power_in"))
    )
    (net (code "55") (name "Net-(U9-TURBOTRANS)") (class "Default")
      (node (ref "R26") (pin "1") (pinfunction "1_1") (pintype "passive"))
      (node (ref "U9") (pin "19") (pinfunction "TURBOTRANS_19") (pintype "input"))
    )
    (net (code "56") (name "Net-(U9-VOADJ)") (class "Default")
      (node (ref "R29") (pin "2") (pinfunction "2_2") (pintype "passive"))
      (node (ref "U9") (pin "18") (pinfunction "VOADJ_18") (pintype "power_in"))
    )
    (net (code "57") (name "Net-(U90-B1)") (class "Default")
      (node (ref "U90") (pin "1") (pinfunction "B1_1") (pintype "passive"))
      (node (ref "U91") (pin "4") (pinfunction "A_4") (pintype "passive"))
    )
    (net (code "58") (name "unconnected-(J1-NC-Pad20)") (class "Default")
      (node (ref "J1") (pin "20") (pinfunction "NC_20") (pintype "power_in+no_connect"))
    )
    (net (code "59") (name "unconnected-(U3-INHIBIT{slash}UVLO-Pad11)") (class "Default")
      (node (ref "U3") (pin "11") (pinfunction "INHIBIT/UVLO_11") (pintype "input+no_connect"))
    )
    (net (code "60") (name "unconnected-(U4-NC-Pad2)") (class "Default")
      (node (ref "U4") (pin "2") (pinfunction "NC_2") (pintype "passive+no_connect"))
    )
    (net (code "61") (name "unconnected-(U4-NC-Pad3)") (class "Default")
      (node (ref "U4") (pin "3") (pinfunction "NC_3") (pintype "passive+no_connect"))
    )
    (net (code "62") (name "unconnected-(U4-NC-Pad4)") (class "Default")
      (node (ref "U4") (pin "4") (pinfunction "NC_4") (pintype "passive+no_connect"))
    )
    (net (code "63") (name "unconnected-(U4-NC-Pad13)") (class "Default")
      (node (ref "U4") (pin "13") (pinfunction "NC_13") (pintype "passive+no_connect"))
    )
    (net (code "64") (name "unconnected-(U4-NC-Pad14)") (class "Default")
      (node (ref "U4") (pin "14") (pinfunction "NC_14") (pintype "passive+no_connect"))
    )
    (net (code "65") (name "unconnected-(U4-NC-Pad17)") (class "Default")
      (node (ref "U4") (pin "17") (pinfunction "NC_17") (pintype "passive+no_connect"))
    )
    (net (code "66") (name "unconnected-(U5-NC-Pad2)") (class "Default")
      (node (ref "U5") (pin "2") (pinfunction "NC_2") (pintype "passive+no_connect"))
    )
    (net (code "67") (name "unconnected-(U5-NC-Pad3)") (class "Default")
      (node (ref "U5") (pin "3") (pinfunction "NC_3") (pintype "passive+no_connect"))
    )
    (net (code "68") (name "unconnected-(U5-NC-Pad4)") (class "Default")
      (node (ref "U5") (pin "4") (pinfunction "NC_4") (pintype "passive+no_connect"))
    )
    (net (code "69") (name "unconnected-(U5-NC-Pad13)") (class "Default")
      (node (ref "U5") (pin "13") (pinfunction "NC_13") (pintype "passive+no_connect"))
    )
    (net (code "70") (name "unconnected-(U5-NC-Pad14)") (class "Default")
      (node (ref "U5") (pin "14") (pinfunction "NC_14") (pintype "passive+no_connect"))
    )
    (net (code "71") (name "unconnected-(U5-NC-Pad17)") (class "Default")
      (node (ref "U5") (pin "17") (pinfunction "NC_17") (pintype "passive+no_connect"))
    )
    (net (code "72") (name "unconnected-(U6-INHIBIT{slash}UVLO-Pad11)") (class "Default")
      (node (ref "U6") (pin "11") (pinfunction "INHIBIT/UVLO_11") (pintype "input+no_connect"))
    )
    (net (code "73") (name "unconnected-(U7-NC-Pad2)") (class "Default")
      (node (ref "U7") (pin "2") (pinfunction "NC_2") (pintype "passive+no_connect"))
    )
    (net (code "74") (name "unconnected-(U7-NC-Pad3)") (class "Default")
      (node (ref "U7") (pin "3") (pinfunction "NC_3") (pintype "passive+no_connect"))
    )
    (net (code "75") (name "unconnected-(U7-NC-Pad4)") (class "Default")
      (node (ref "U7") (pin "4") (pinfunction "NC_4") (pintype "passive+no_connect"))
    )
    (net (code "76") (name "unconnected-(U7-NC-Pad13)") (class "Default")
      (node (ref "U7") (pin "13") (pinfunction "NC_13") (pintype "passive+no_connect"))
    )
    (net (code "77") (name "unconnected-(U7-NC-Pad14)") (class "Default")
      (node (ref "U7") (pin "14") (pinfunction "NC_14") (pintype "passive+no_connect"))
    )
    (net (code "78") (name "unconnected-(U7-NC-Pad17)") (class "Default")
      (node (ref "U7") (pin "17") (pinfunction "NC_17") (pintype "passive+no_connect"))
    )
    (net (code "79") (name "unconnected-(U9-CLKIO-Pad5)") (class "Default")
      (node (ref "U9") (pin "5") (pinfunction "CLKIO_5") (pintype "input+no_connect"))
    )
    (net (code "80") (name "unconnected-(U9-COMP-Pad3)") (class "Default")
      (node (ref "U9") (pin "3") (pinfunction "COMP_3") (pintype "input+no_connect"))
    )
    (net (code "81") (name "unconnected-(U9-INHIBIT{slash}UVLO-Pad21)") (class "Default")
      (node (ref "U9") (pin "21") (pinfunction "INHIBIT/UVLO_21") (pintype "input+no_connect"))
    )
    (net (code "82") (name "unconnected-(U9-SHARE-Pad2)") (class "Default")
      (node (ref "U9") (pin "2") (pinfunction "SHARE_2") (pintype "input+no_connect"))
    )
    (net (code "83") (name "unconnected-(U90-B0-Pad3)") (class "Default")
      (node (ref "U90") (pin "3") (pinfunction "B0_3") (pintype "passive+no_connect"))
    )
  )
)
